# Connectors.net
KiCad netlist of a schematic drawn in Altium Designer
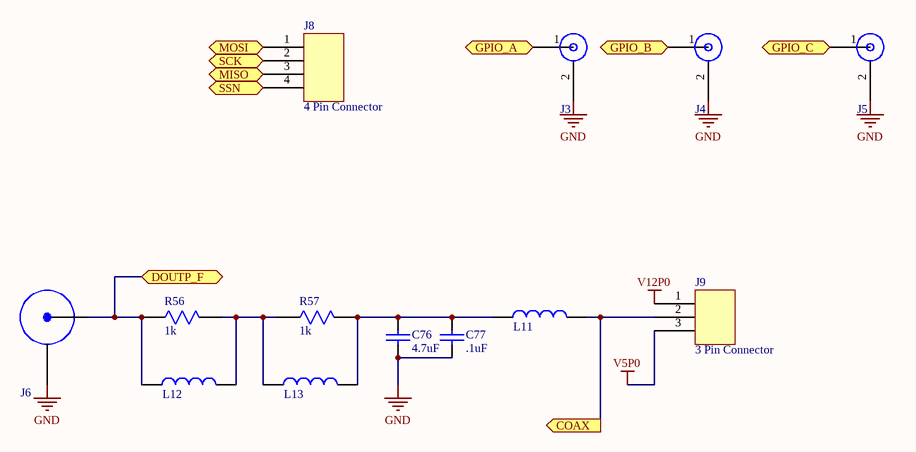
[diagram p0: Connectors.SchDoc]

(export (version "E")
  (design (tool "Eeschema 10.0.6"))
  (components
    (comp (ref "C76")
      (value "4.7uF")
      (footprint "SMD Capacitor 0603")
      (libsource (lib "DA_Component_Library") (part "Capacitor"))
    )
    (comp (ref "C77")
      (value ".1uF")
      (footprint "SMD CAP 0402")
      (libsource (lib "DA_Component_Library") (part "Capacitor"))
    )
    (comp (ref "J3")
      (value "SMA")
      (footprint "SMA Right Angle Through Hole")
      (libsource (lib "DA_Component_Library") (part "SMA"))
    )
    (comp (ref "J4")
      (value "SMA")
      (footprint "SMA Right Angle Through Hole")
      (libsource (lib "DA_Component_Library") (part "SMA"))
    )
    (comp (ref "J5")
      (value "SMA")
      (footprint "SMA Right Angle Through Hole")
      (libsource (lib "DA_Component_Library") (part "SMA"))
    )
    (comp (ref "J6")
      (value "Coax Connector")
      (footprint "SSMCX EDGE")
      (libsource (lib "DA_Component_Library") (part "Coax Connector"))
    )
    (comp (ref "J8")
      (value "4 Pin Connector")
      (footprint "4Pin Verital 0.1\"")
      (libsource (lib "DA_Component_Library") (part "4 Pin Connector"))
    )
    (comp (ref "J9")
      (value "3 Pin Connector")
      (footprint "3Pin Verital 0.1\" JUMOER")
      (libsource (lib "DA_Component_Library") (part "3 Pin Connector"))
    )
    (comp (ref "L11")
      (value "Ferrite Bead")
      (footprint "BLM18KG601SN1D")
      (libsource (lib "DA_Component_Library") (part "Ferrite Bead"))
    )
    (comp (ref "L12")
      (value "Ferrite Bead")
      (footprint "CIG21L4R7MNE")
      (libsource (lib "DA_Component_Library") (part "Ferrite Bead"))
    )
    (comp (ref "L13")
      (value "Ferrite Bead")
      (footprint "CBC3225T101MR")
      (libsource (lib "DA_Component_Library") (part "Ferrite Bead"))
    )
    (comp (ref "R56")
      (value "1k")
      (footprint "SMD Resistor 0603")
      (libsource (lib "DA_Component_Library") (part "Resistor"))
    )
    (comp (ref "R57")
      (value "1k")
      (footprint "SMD Resistor 0603")
      (libsource (lib "DA_Component_Library") (part "Resistor"))
    )
  )
  (nets
    (net (code "1") (name "/COAX") (class "Default")
      (node (ref "J9") (pin "2") (pinfunction "2_2") (pintype "passive"))
      (node (ref "L11") (pin "2") (pinfunction "2_2") (pintype "passive"))
    )
    (net (code "2") (name "/DOUTP_F") (class "Default")
      (node (ref "J6") (pin "0") (pinfunction "0_0") (pintype "passive"))
      (node (ref "L12") (pin "1") (pinfunction "1_1") (pintype "passive"))
      (node (ref "R56") (pin "0") (pinfunction "0_0") (pintype "passive"))
    )
    (net (code "3") (name "/GPIO_A") (class "Default")
      (node (ref "J3") (pin "1") (pinfunction "1_1") (pintype "passive"))
    )
    (net (code "4") (name "/GPIO_B") (class "Default")
      (node (ref "J4") (pin "1") (pinfunction "1_1") (pintype "passive"))
    )
    (net (code "5") (name "/GPIO_C") (class "Default")
      (node (ref "J5") (pin "1") (pinfunction "1_1") (pintype "passive"))
    )
    (net (code "6") (name "/MISO") (class "Default")
      (node (ref "J8") (pin "3") (pinfunction "3_3") (pintype "passive"))
    )
    (net (code "7") (name "/MOSI") (class "Default")
      (node (ref "J8") (pin "1") (pinfunction "1_1") (pintype "passive"))
    )
    (net (code "8") (name "/SCK") (class "Default")
      (node (ref "J8") (pin "2") (pinfunction "2_2") (pintype "passive"))
    )
    (net (code "9") (name "/SSN") (class "Default")
      (node (ref "J8") (pin "4") (pinfunction "4_4") (pintype "passive"))
    )
    (net (code "10") (name "GND") (class "Default")
      (node (ref "C76") (pin "1") (pinfunction "1_1") (pintype "passive"))
      (node (ref "C77") (pin "1") (pinfunction "1_1") (pintype "passive"))
      (node (ref "J3") (pin "2") (pinfunction "2_2") (pintype "passive"))
      (node (ref "J4") (pin "2") (pinfunction "2_2") (pintype "passive"))
      (node (ref "J5") (pin "2") (pinfunction "2_2") (pintype "passive"))
      (node (ref "J6") (pin "1") (pinfunction "1_1") (pintype "passive"))
    )
    (net (code "11") (name "Net-(C76-Pad0)") (class "Default")
      (node (ref "C76") (pin "0") (pinfunction "0_0") (pintype "passive"))
      (node (ref "C77") (pin "0") (pinfunction "0_0") (pintype "passive"))
      (node (ref "L11") (pin "1") (pinfunction "1_1") (pintype "passive"))
      (node (ref "L13") (pin "2") (pinfunction "2_2") (pintype "passive"))
      (node (ref "R57") (pin "1") (pinfunction "1_1") (pintype "passive"))
    )
    (net (code "12") (name "Net-(L12-Pad2)") (class "Default")
      (node (ref "L12") (pin "2") (pinfunction "2_2") (pintype "passive"))
      (node (ref "L13") (pin "1") (pinfunction "1_1") (pintype "passive"))
      (node (ref "R56") (pin "1") (pinfunction "1_1") (pintype "passive"))
      (node (ref "R57") (pin "0") (pinfunction "0_0") (pintype "passive"))
    )
    (net (code "13") (name "V5P0") (class "Default")
      (node (ref "J9") (pin "3") (pinfunction "3_3") (pintype "passive"))
    )
    (net (code "14") (name "V12P0") (class "Default")
      (node (ref "J9") (pin "1") (pinfunction "1_1") (pintype "passive"))
    )
  )
)
